# LTM8032_3V8.net
KiCad netlist of a schematic drawn in Altium Designer
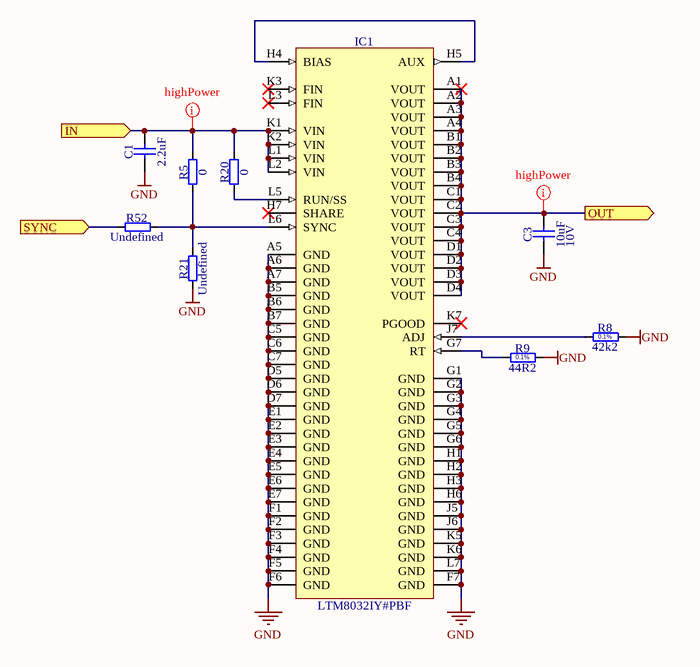
[diagram p0: LTM8032_3V8.SchDoc]

(export (version "E")
  (design (tool "Eeschema 10.0.6"))
  (components
    (comp (ref "C1")
      (value "2.2uF")
      (footprint "CAPC3216X180N")
      (description "Non-polarised capacitor")
      (fields
        (field (name "PART NUMBER") "CC1206_2.2UF_50V_10%_X7R_YUDEN_UMK316B7225KLHT")
        (field (name "VOLTAGE") "50V")
        (field (name "AUTHOR") "CERN DEM JLC")
      )
      (libsource (lib "Capacitors") (part "Capacitor - non polarized"))
    )
    (comp (ref "C3")
      (value "10uF")
      (footprint "CAPC2012X135N")
      (description "Non-polarised capacitor")
      (fields
        (field (name "PART NUMBER") "CC0805_10UF_10V_10%_X7R")
        (field (name "VOLTAGE") "10V")
        (field (name "TOLERANCE") "±10%")
        (field (name "AUTHOR") "CERN DEM JLC")
      )
      (libsource (lib "Capacitors") (part "Capacitor - non polarized"))
    )
    (comp (ref "IC1")
      (value "LTM8032IY#PBF")
      (footprint "BGA71C127P7X11_900X1500X362")
      (description "3V-36V To 0.8V-10V, Iout 2A Ultralow Noise EMC Compliant DC/DC uModule")
      (fields (field (name "MANUFACTURER") "LINEAR TECHNOLOGY") (field (name "AUTHOR") "CERN DEM BC"))
      (libsource (lib "ICs And Semiconductors") (part "LTM8032"))
    )
    (comp (ref "R5")
      (value "0")
      (footprint "RESC1608X55N")
      (description "Resistor")
      (fields
        (field (name "PART NUMBER") "R0603_0R_JUMPER")
        (field (name "MANUFACTURER") "GENERIC")
        (field (name "AUTHOR") "CERN DEM JLC")
      )
      (libsource (lib "Resistors") (part "Resistor"))
    )
    (comp (ref "R8")
      (value "42k2")
      (footprint "RESC1608X55N")
      (description "Resistor - 0.1%")
      (fields
        (field (name "PART NUMBER") "R0603_42K2_0.1%_0.063W_10PPM")
        (field (name "POWER") "0.063W")
        (field (name "AUTHOR") "CERN DEM JLC")
      )
      (libsource (lib "Resistors") (part "Resistor - 0.1%"))
    )
    (comp (ref "R9")
      (value "44R2")
      (footprint "RESC1608X55N")
      (description "Resistor - 0.1%")
      (fields
        (field (name "PART NUMBER") "R0603_44R2_0.1%_0.063W_10PPM")
        (field (name "POWER") "0.063W")
        (field (name "AUTHOR") "CERN DEM JLC")
      )
      (libsource (lib "Resistors") (part "Resistor - 0.1%"))
    )
    (comp (ref "R20")
      (value "0")
      (footprint "RESC1608X55N")
      (description "Resistor")
      (fields
        (field (name "PART NUMBER") "R0603_0R_JUMPER")
        (field (name "MANUFACTURER") "GENERIC")
        (field (name "AUTHOR") "CERN DEM JLC")
      )
      (libsource (lib "Resistors") (part "Resistor"))
    )
    (comp (ref "R21")
      (value "Undefined")
      (footprint "RESC1608X55N")
      (description "Resistor")
      (fields (field (name "PART NUMBER") "R0603_NO-VALUE") (field (name "AUTHOR") "CERN DEM JLC"))
      (libsource (lib "Resistors") (part "Resistor"))
    )
    (comp (ref "R52")
      (value "Undefined")
      (footprint "RESC1608X55N")
      (description "Resistor")
      (fields (field (name "PART NUMBER") "R0603_NO-VALUE") (field (name "AUTHOR") "CERN DEM JLC"))
      (libsource (lib "Resistors") (part "Resistor"))
    )
  )
  (nets
    (net (code "1") (name "/IN") (class "Default")
      (node (ref "C1") (pin "2") (pinfunction "2_2") (pintype "passive"))
      (node (ref "IC1") (pin "K1") (pinfunction "VIN_K1") (pintype "input"))
      (node (ref "IC1") (pin "K2") (pinfunction "VIN_K2") (pintype "input"))
      (node (ref "IC1") (pin "L1") (pinfunction "VIN_L1") (pintype "input"))
      (node (ref "IC1") (pin "L2") (pinfunction "VIN_L2") (pintype "input"))
      (node (ref "R20") (pin "2") (pinfunction "2_2") (pintype "passive"))
      (node (ref "R5") (pin "2") (pinfunction "2_2") (pintype "passive"))
    )
    (net (code "2") (name "/OUT") (class "Default")
      (node (ref "C3") (pin "2") (pinfunction "2_2") (pintype "passive"))
      (node (ref "IC1") (pin "A1") (pinfunction "VOUT_A1") (pintype "power_in"))
      (node (ref "IC1") (pin "A2") (pinfunction "VOUT_A2") (pintype "power_in"))
      (node (ref "IC1") (pin "A3") (pinfunction "VOUT_A3") (pintype "power_in"))
      (node (ref "IC1") (pin "A4") (pinfunction "VOUT_A4") (pintype "power_in"))
      (node (ref "IC1") (pin "B1") (pinfunction "VOUT_B1") (pintype "power_in"))
      (node (ref "IC1") (pin "B2") (pinfunction "VOUT_B2") (pintype "power_in"))
      (node (ref "IC1") (pin "B3") (pinfunction "VOUT_B3") (pintype "power_in"))
      (node (ref "IC1") (pin "B4") (pinfunction "VOUT_B4") (pintype "power_in"))
      (node (ref "IC1") (pin "C1") (pinfunction "VOUT_C1") (pintype "power_in"))
      (node (ref "IC1") (pin "C2") (pinfunction "VOUT_C2") (pintype "power_in"))
      (node (ref "IC1") (pin "C3") (pinfunction "VOUT_C3") (pintype "power_in"))
      (node (ref "IC1") (pin "C4") (pinfunction "VOUT_C4") (pintype "power_in"))
      (node (ref "IC1") (pin "D1") (pinfunction "VOUT_D1") (pintype "power_in"))
      (node (ref "IC1") (pin "D2") (pinfunction "VOUT_D2") (pintype "power_in"))
      (node (ref "IC1") (pin "D3") (pinfunction "VOUT_D3") (pintype "power_in"))
      (node (ref "IC1") (pin "D4") (pinfunction "VOUT_D4") (pintype "power_in"))
    )
    (net (code "3") (name "/SYNC") (class "Default")
      (node (ref "R52") (pin "1") (pinfunction "1_1") (pintype "passive"))
    )
    (net (code "4") (name "GND") (class "Default")
      (node (ref "C1") (pin "1") (pinfunction "1_1") (pintype "passive"))
      (node (ref "C3") (pin "1") (pinfunction "1_1") (pintype "passive"))
      (node (ref "IC1") (pin "A5") (pinfunction "GND_A5") (pintype "power_in"))
      (node (ref "IC1") (pin "A6") (pinfunction "GND_A6") (pintype "power_in"))
      (node (ref "IC1") (pin "A7") (pinfunction "GND_A7") (pintype "power_in"))
      (node (ref "IC1") (pin "B5") (pinfunction "GND_B5") (pintype "power_in"))
      (node (ref "IC1") (pin "B6") (pinfunction "GND_B6") (pintype "power_in"))
      (node (ref "IC1") (pin "B7") (pinfunction "GND_B7") (pintype "power_in"))
      (node (ref "IC1") (pin "C5") (pinfunction "GND_C5") (pintype "power_in"))
      (node (ref "IC1") (pin "C6") (pinfunction "GND_C6") (pintype "power_in"))
      (node (ref "IC1") (pin "C7") (pinfunction "GND_C7") (pintype "power_in"))
      (node (ref "IC1") (pin "D5") (pinfunction "GND_D5") (pintype "power_in"))
      (node (ref "IC1") (pin "D6") (pinfunction "GND_D6") (pintype "power_in"))
      (node (ref "IC1") (pin "D7") (pinfunction "GND_D7") (pintype "power_in"))
      (node (ref "IC1") (pin "E1") (pinfunction "GND_E1") (pintype "power_in"))
      (node (ref "IC1") (pin "E2") (pinfunction "GND_E2") (pintype "power_in"))
      (node (ref "IC1") (pin "E3") (pinfunction "GND_E3") (pintype "power_in"))
      (node (ref "IC1") (pin "E4") (pinfunction "GND_E4") (pintype "power_in"))
      (node (ref "IC1") (pin "E5") (pinfunction "GND_E5") (pintype "power_in"))
      (node (ref "IC1") (pin "E6") (pinfunction "GND_E6") (pintype "power_in"))
      (node (ref "IC1") (pin "E7") (pinfunction "GND_E7") (pintype "power_in"))
      (node (ref "IC1") (pin "F1") (pinfunction "GND_F1") (pintype "power_in"))
      (node (ref "IC1") (pin "F2") (pinfunction "GND_F2") (pintype "power_in"))
      (node (ref "IC1") (pin "F3") (pinfunction "GND_F3") (pintype "power_in"))
      (node (ref "IC1") (pin "F4") (pinfunction "GND_F4") (pintype "power_in"))
      (node (ref "IC1") (pin "F5") (pinfunction "GND_F5") (pintype "power_in"))
      (node (ref "IC1") (pin "F6") (pinfunction "GND_F6") (pintype "power_in"))
      (node (ref "IC1") (pin "F7") (pinfunction "GND_F7") (pintype "power_in"))
      (node (ref "IC1") (pin "G1") (pinfunction "GND_G1") (pintype "power_in"))
      (node (ref "IC1") (pin "G2") (pinfunction "GND_G2") (pintype "power_in"))
      (node (ref "IC1") (pin "G3") (pinfunction "GND_G3") (pintype "power_in"))
      (node (ref "IC1") (pin "G4") (pinfunction "GND_G4") (pintype "power_in"))
      (node (ref "IC1") (pin "G5") (pinfunction "GND_G5") (pintype "power_in"))
      (node (ref "IC1") (pin "G6") (pinfunction "GND_G6") (pintype "power_in"))
      (node (ref "IC1") (pin "H1") (pinfunction "GND_H1") (pintype "power_in"))
      (node (ref "IC1") (pin "H2") (pinfunction "GND_H2") (pintype "power_in"))
      (node (ref "IC1") (pin "H3") (pinfunction "GND_H3") (pintype "power_in"))
      (node (ref "IC1") (pin "H6") (pinfunction "GND_H6") (pintype "power_in"))
      (node (ref "IC1") (pin "J5") (pinfunction "GND_J5") (pintype "power_in"))
      (node (ref "IC1") (pin "J6") (pinfunction "GND_J6") (pintype "power_in"))
      (node (ref "IC1") (pin "K5") (pinfunction "GND_K5") (pintype "power_in"))
      (node (ref "IC1") (pin "K6") (pinfunction "GND_K6") (pintype "power_in"))
      (node (ref "IC1") (pin "L7") (pinfunction "GND_L7") (pintype "power_in"))
      (node (ref "R21") (pin "1") (pinfunction "1_1") (pintype "passive"))
      (node (ref "R8") (pin "2") (pinfunction "2_2") (pintype "passive"))
      (node (ref "R9") (pin "2") (pinfunction "2_2") (pintype "passive"))
    )
    (net (code "5") (name "Net-(IC1-ADJ)") (class "Default")
      (node (ref "IC1") (pin "J7") (pinfunction "ADJ_J7") (pintype "input"))
      (node (ref "R8") (pin "1") (pinfunction "1_1") (pintype "passive"))
    )
    (net (code "6") (name "Net-(IC1-AUX)") (class "Default")
      (node (ref "IC1") (pin "H4") (pinfunction "BIAS_H4") (pintype "input"))
      (node (ref "IC1") (pin "H5") (pinfunction "AUX_H5") (pintype "output"))
    )
    (net (code "7") (name "Net-(IC1-RT)") (class "Default")
      (node (ref "IC1") (pin "G7") (pinfunction "RT_G7") (pintype "input"))
      (node (ref "R9") (pin "1") (pinfunction "1_1") (pintype "passive"))
    )
    (net (code "8") (name "Net-(IC1-RUN{slash}SS)") (class "Default")
      (node (ref "IC1") (pin "L5") (pinfunction "RUN/SS_L5") (pintype "input"))
      (node (ref "R20") (pin "1") (pinfunction "1_1") (pintype "passive"))
    )
    (net (code "9") (name "Net-(IC1-SYNC)") (class "Default")
      (node (ref "IC1") (pin "L6") (pinfunction "SYNC_L6") (pintype "input"))
      (node (ref "R21") (pin "2") (pinfunction "2_2") (pintype "passive"))
      (node (ref "R5") (pin "1") (pinfunction "1_1") (pintype "passive"))
      (node (ref "R52") (pin "2") (pinfunction "2_2") (pintype "passive"))
    )
    (net (code "10") (name "unconnected-(IC1-FIN-PadK3)") (class "Default")
      (node (ref "IC1") (pin "K3") (pinfunction "FIN_K3") (pintype "input+no_connect"))
    )
    (net (code "11") (name "unconnected-(IC1-FIN-PadL3)") (class "Default")
      (node (ref "IC1") (pin "L3") (pinfunction "FIN_L3") (pintype "input+no_connect"))
    )
    (net (code "12") (name "unconnected-(IC1-PGOOD-PadK7)") (class "Default")
      (node (ref "IC1") (pin "K7") (pinfunction "PGOOD_K7") (pintype "open_collector+no_connect"))
    )
    (net (code "13") (name "unconnected-(IC1-SHARE-PadH7)") (class "Default")
      (node (ref "IC1") (pin "H7") (pinfunction "SHARE_H7") (pintype "passive+no_connect"))
    )
  )
)
